# Wacky_Hat_Schematic.net
KiCad netlist of a schematic drawn in Altium Designer
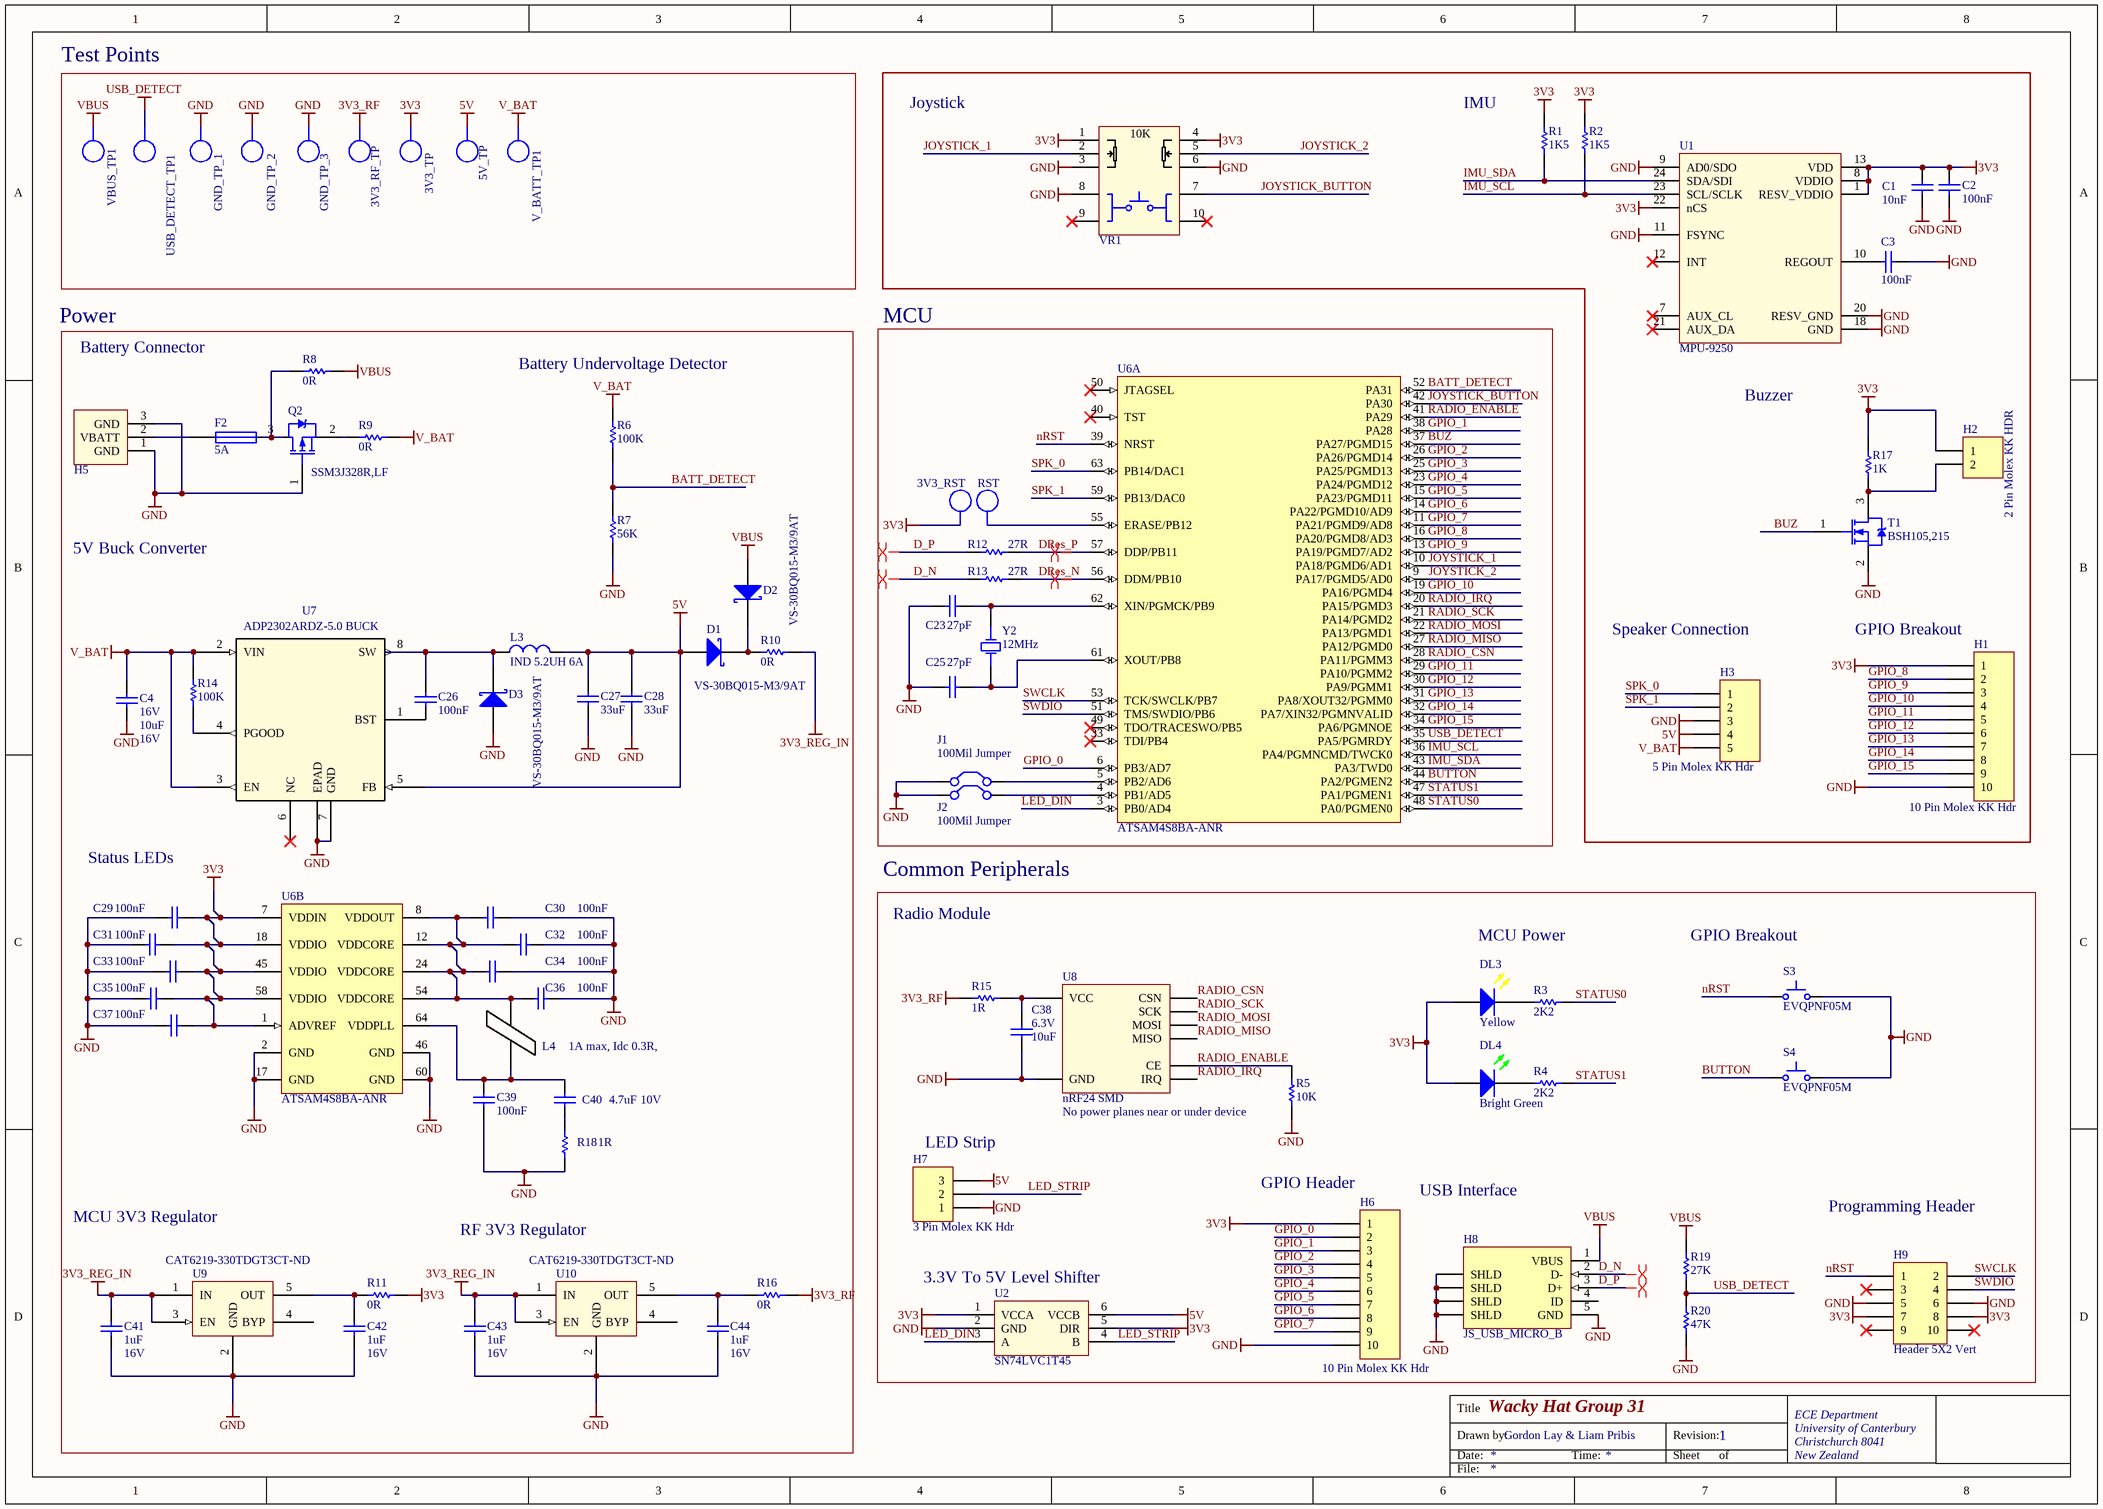
[diagram p0: Wacky Hat Schematic.SchDoc]

(export (version "E")
  (design (tool "Eeschema 10.0.6"))
  (components
    (comp (ref "3V3_RF_TP")
      (value "TP")
      (footprint "TP_1206")
      (description "Test-Point 3.3x1.6x2.1mm SMD")
      (fields
        (field (name "MANUFACTURER") "Harwin Inc")
        (field (name "MANUFACTURER PART NUMBER") "S1751-46R")
      )
      (libsource (lib "ECE AD19Components_19V1") (part "TP_1206"))
    )
    (comp (ref "3V3_RST")
      (value "TP")
      (footprint "TP_1206")
      (description "Test-Point 3.3x1.6x2.1mm SMD")
      (fields
        (field (name "MANUFACTURER") "Harwin Inc")
        (field (name "MANUFACTURER PART NUMBER") "S1751-46R")
      )
      (libsource (lib "ECE AD19Components_19V1") (part "TP_1206"))
    )
    (comp (ref "3V3_TP")
      (value "TP")
      (footprint "TP_1206")
      (description "Test-Point 3.3x1.6x2.1mm SMD")
      (fields
        (field (name "MANUFACTURER") "Harwin Inc")
        (field (name "MANUFACTURER PART NUMBER") "S1751-46R")
      )
      (libsource (lib "ECE AD19Components_19V1") (part "TP_1206"))
    )
    (comp (ref "5V_TP")
      (value "TP")
      (footprint "TP_1206")
      (description "Test-Point 3.3x1.6x2.1mm SMD")
      (fields
        (field (name "MANUFACTURER") "Harwin Inc")
        (field (name "MANUFACTURER PART NUMBER") "S1751-46R")
      )
      (libsource (lib "ECE AD19Components_19V1") (part "TP_1206"))
    )
    (comp (ref "C1")
      (value "10nF")
      (footprint "CAPC1608L")
      (description "CAP CER 10nF X7R +-10% 50V 0603")
      (libsource (lib "ECE AD19Components_19V1") (part "CC_10nF_0603"))
    )
    (comp (ref "C2")
      (value "100nF")
      (footprint "CAPC1608L")
      (description "CAP CER 100nF X7R +-10% 50V 0603")
      (libsource (lib "ECE AD19Components_19V1") (part "CC_100nF_0603"))
    )
    (comp (ref "C3")
      (value "100nF")
      (footprint "CAPC1608L")
      (description "CAP CER 100nF X7R +-10% 50V 0603")
      (libsource (lib "ECE AD19Components_19V1") (part "CC_100nF_0603"))
    )
    (comp (ref "C4")
      (value "10uF")
      (footprint "CAPC2012L")
      (description "CAP CER 10uF X5R 16V 0805")
      (fields
        (field (name "MANUFACTURER") "Samsung Electro-Mechanics")
        (field (name "MANUFACTURER PART NUMBER") "CL21A106KOQNNWE")
        (field (name "VOLTAGE - RATED") "16V")
        (field (name "MAX VOLTAGE") "16V")
      )
      (libsource (lib "ENCE461AD19_19V2") (part "CC_10uF_16V_0805"))
    )
    (comp (ref "C23")
      (value "27pF")
      (footprint "CAPC1608L")
      (description "CAP CER 27pF NPO/COG +-5% 50V 0603")
      (libsource (lib "ECE AD19Components_19V1") (part "CC_27pF_0603"))
    )
    (comp (ref "C25")
      (value "27pF")
      (footprint "CAPC1608L")
      (description "CAP CER 27pF NPO/COG +-5% 50V 0603")
      (libsource (lib "ECE AD19Components_19V1") (part "CC_27pF_0603"))
    )
    (comp (ref "C26")
      (value "100nF")
      (footprint "CAPC1608L")
      (description "CAP CER 100nF X7R +-10% 50V 0603")
      (libsource (lib "ECE AD19Components_19V1") (part "CC_100nF_0603"))
    )
    (comp (ref "C27")
      (value "33uF")
      (footprint "CAPC2012L")
      (description "CAP CER 33uF X5R 6V3 0805")
      (fields
        (field (name "MANUFACTURER") "TDK Corporation")
        (field (name "MANUFACTURER PART NUMBER") "C2012X5R0J336M125AC")
      )
      (libsource (lib "ENCE461AD19_19V2") (part "CC_33uF_6V3_0805"))
    )
    (comp (ref "C28")
      (value "33uF")
      (footprint "CAPC2012L")
      (description "CAP CER 33uF X5R 6V3 0805")
      (fields
        (field (name "MANUFACTURER") "TDK Corporation")
        (field (name "MANUFACTURER PART NUMBER") "C2012X5R0J336M125AC")
      )
      (libsource (lib "ENCE461AD19_19V2") (part "CC_33uF_6V3_0805"))
    )
    (comp (ref "C29")
      (value "100nF")
      (footprint "CAPC1608L")
      (description "CAP CER 100nF X7R +-10% 50V 0603")
      (libsource (lib "ECE AD19Components_19V1") (part "CC_100nF_0603"))
    )
    (comp (ref "C30")
      (value "100nF")
      (footprint "CAPC1608L")
      (description "CAP CER 100nF X7R +-10% 50V 0603")
      (libsource (lib "ECE AD19Components_19V1") (part "CC_100nF_0603"))
    )
    (comp (ref "C31")
      (value "100nF")
      (footprint "CAPC1608L")
      (description "CAP CER 100nF X7R +-10% 50V 0603")
      (libsource (lib "ECE AD19Components_19V1") (part "CC_100nF_0603"))
    )
    (comp (ref "C32")
      (value "100nF")
      (footprint "CAPC1608L")
      (description "CAP CER 100nF X7R +-10% 50V 0603")
      (libsource (lib "ECE AD19Components_19V1") (part "CC_100nF_0603"))
    )
    (comp (ref "C33")
      (value "100nF")
      (footprint "CAPC1608L")
      (description "CAP CER 100nF X7R +-10% 50V 0603")
      (libsource (lib "ECE AD19Components_19V1") (part "CC_100nF_0603"))
    )
    (comp (ref "C34")
      (value "100nF")
      (footprint "CAPC1608L")
      (description "CAP CER 100nF X7R +-10% 50V 0603")
      (libsource (lib "ECE AD19Components_19V1") (part "CC_100nF_0603"))
    )
    (comp (ref "C35")
      (value "100nF")
      (footprint "CAPC1608L")
      (description "CAP CER 100nF X7R +-10% 50V 0603")
      (libsource (lib "ECE AD19Components_19V1") (part "CC_100nF_0603"))
    )
    (comp (ref "C36")
      (value "100nF")
      (footprint "CAPC1608L")
      (description "CAP CER 100nF X7R +-10% 50V 0603")
      (libsource (lib "ECE AD19Components_19V1") (part "CC_100nF_0603"))
    )
    (comp (ref "C37")
      (value "100nF")
      (footprint "CAPC1608L")
      (description "CAP CER 100nF X7R +-10% 50V 0603")
      (libsource (lib "ECE AD19Components_19V1") (part "CC_100nF_0603"))
    )
    (comp (ref "C38")
      (value "10uF")
      (footprint "CAPC1608L")
      (description "CAP CER 10UF X5R +-20% 6V3 0603")
      (fields (field (name "VOLTAGE - RATED") "6.3V"))
      (libsource (lib "ECE AD19Components_19V1") (part "CC_10uF_0603"))
    )
    (comp (ref "C39")
      (value "100nF")
      (footprint "CAPC1608L")
      (description "CAP CER 100nF X7R +-10% 50V 0603")
      (libsource (lib "ECE AD19Components_19V1") (part "CC_100nF_0603"))
    )
    (comp (ref "C40")
      (value "4.7uF")
      (footprint "CAPC1608N")
      (description "CAP CER 4.7uF X5R +-20%  10V 0603")
      (fields (field (name "MAX VOLTAGE") "10V"))
      (libsource (lib "ECE AD19Components_19V1") (part "CC_4.7uF_0603"))
    )
    (comp (ref "C41")
      (value "1uF")
      (footprint "CAPC1608L")
      (description "CAP CER 1uF Y5V -20% +80% 16V 0603")
      (fields (field (name "MAX VOLTAGE") "16V"))
      (libsource (lib "ECE AD19Components_19V1") (part "CC_1uF_0603"))
    )
    (comp (ref "C42")
      (value "1uF")
      (footprint "CAPC1608L")
      (description "CAP CER 1uF Y5V -20% +80% 16V 0603")
      (fields (field (name "MAX VOLTAGE") "16V"))
      (libsource (lib "ECE AD19Components_19V1") (part "CC_1uF_0603"))
    )
    (comp (ref "C43")
      (value "1uF")
      (footprint "CAPC1608L")
      (description "CAP CER 1uF Y5V -20% +80% 16V 0603")
      (fields (field (name "MAX VOLTAGE") "16V"))
      (libsource (lib "ECE AD19Components_19V1") (part "CC_1uF_0603"))
    )
    (comp (ref "C44")
      (value "1uF")
      (footprint "CAPC1608L")
      (description "CAP CER 1uF Y5V -20% +80% 16V 0603")
      (fields (field (name "MAX VOLTAGE") "16V"))
      (libsource (lib "ECE AD19Components_19V1") (part "CC_1uF_0603"))
    )
    (comp (ref "D1")
      (value "VS-30BQ015-M3/9AT")
      (footprint "SMC")
      (description "DIODE, SCHOTTKY, 3A, 15V, DO-214AB / SMC")
      (fields (field (name "MANUFACTURER") "Vishay Semiconductors"))
      (libsource (lib "ECE AD19Components_19V1") (part "DS_VS-30BQ015-M3"))
    )
    (comp (ref "D2")
      (value "VS-30BQ015-M3/9AT")
      (footprint "SMC")
      (description "DIODE, SCHOTTKY, 3A, 15V, DO-214AB / SMC")
      (fields (field (name "MANUFACTURER") "Vishay Semiconductors"))
      (libsource (lib "ECE AD19Components_19V1") (part "DS_VS-30BQ015-M3"))
    )
    (comp (ref "D3")
      (value "VS-30BQ015-M3/9AT")
      (footprint "SMC")
      (description "DIODE, SCHOTTKY, 3A, 15V, DO-214AB / SMC")
      (fields (field (name "MANUFACTURER") "Vishay Semiconductors"))
      (libsource (lib "ECE AD19Components_19V1") (part "DS_VS-30BQ015-M3"))
    )
    (comp (ref "DL3")
      (value "Yellow")
      (footprint "WL-SMCW0603")
      (description "LED Yellow 120mcd 0603 SMD")
      (fields
        (field (name "MANUFACTURER") "WURTH ELEKTRONIK")
        (field (name "MANUFACTURER PART NUMBER") "150060YS75000")
        (field (name "LED COLOUR") "Yellow")
      )
      (libsource (lib "ECE AD19Components_19V1") (part "DL_150060YS75000"))
    )
    (comp (ref "DL4")
      (value "Bright Green")
      (footprint "WL-SMCW0603")
      (description "LED Bright Green 40mcd 0603 SMD")
      (fields
        (field (name "MANUFACTURER") "WURTH ELEKTRONIK")
        (field (name "MANUFACTURER PART NUMBER") "150060VS75000")
        (field (name "LED COLOUR") "Bright Green")
      )
      (libsource (lib "ECE AD19Components_19V1") (part "DL_150060VS75000"))
    )
    (comp (ref "F2")
      (value "5A")
      (footprint "RESC3216N")
      (description "Fuse 5.0A Fast Acting 1206 SMD")
      (fields (field (name "MANUFACTURER PART NUMBER") "C1F5") (field (name "MANUFACTURER") "Bel TRP"))
      (libsource (lib "ECE AD19Components_19V1") (part "FS_Fuse_5.0A"))
    )
    (comp (ref "GND_TP_1")
      (value "TP")
      (footprint "TP_1206")
      (description "Test-Point 3.3x1.6x2.1mm SMD")
      (fields
        (field (name "MANUFACTURER") "Harwin Inc")
        (field (name "MANUFACTURER PART NUMBER") "S1751-46R")
      )
      (libsource (lib "ECE AD19Components_19V1") (part "TP_1206"))
    )
    (comp (ref "GND_TP_2")
      (value "TP")
      (footprint "TP_1206")
      (description "Test-Point 3.3x1.6x2.1mm SMD")
      (fields
        (field (name "MANUFACTURER") "Harwin Inc")
        (field (name "MANUFACTURER PART NUMBER") "S1751-46R")
      )
      (libsource (lib "ECE AD19Components_19V1") (part "TP_1206"))
    )
    (comp (ref "GND_TP_3")
      (value "TP")
      (footprint "TP_1206")
      (description "Test-Point 3.3x1.6x2.1mm SMD")
      (fields
        (field (name "MANUFACTURER") "Harwin Inc")
        (field (name "MANUFACTURER PART NUMBER") "S1751-46R")
      )
      (libsource (lib "ECE AD19Components_19V1") (part "TP_1206"))
    )
    (comp (ref "H1")
      (value "10 Pin Molex KK Hdr")
      (footprint "MOLEX_KK_10_HDR")
      (description "CONN HEADER 10POS 2.54mm VERT_ Thru Hole")
      (libsource (lib "ECE AD19Components_19V1") (part "JA_MOLEX_KK_10POS"))
    )
    (comp (ref "H2")
      (value "2 Pin Molex KK HDR")
      (footprint "MOLEX_KK_2_HDR")
      (description "CONN HEADER 2POS 2.54mm VERT_Thru Hole")
      (libsource (lib "ECE AD19Components_19V1") (part "JA_MOLEX_KK_2POS"))
    )
    (comp (ref "H3")
      (value "5 Pin Molex KK Hdr")
      (footprint "MOLEX_KK_5_HDR")
      (description "CONN HEADER 5POS 2.54mm VERT_Thru Hole")
      (fields (field (name "MANUFACTURER") "Molex"))
      (libsource (lib "ECE AD19Components_19V1") (part "JA_MOLEX_KK_5POS"))
    )
    (comp (ref "H5")
      (value "Battery_HEADER_3pin")
      (footprint "BATT_HEADER_3POS")
      (description "3Pin Header 2.54mm spacing")
      (libsource (lib "ENCE461AD19_19V2") (part "Battery_HEADER_3pin"))
    )
    (comp (ref "H6")
      (value "10 Pin Molex KK Hdr")
      (footprint "MOLEX_KK_10_HDR")
      (description "CONN HEADER 10POS 2.54mm VERT_ Thru Hole")
      (libsource (lib "ECE AD19Components_19V1") (part "JA_MOLEX_KK_10POS"))
    )
    (comp (ref "H7")
      (value "3 Pin Molex KK Hdr")
      (footprint "MOLEX_KK_3_HDR")
      (description "CONN HEADER 3POS 2.54mm VERT_Thru Hole")
      (fields (field (name "MANUFACTURER") "Molex"))
      (libsource (lib "ECE AD19Components_19V1") (part "JA_MOLEX_KK_3POS"))
    )
    (comp (ref "H8")
      (value "JS_USB_MICRO_B")
      (footprint "FCI_USB_10118194-0001LF")
      (description "CONN USB MICRO B RECPT SMT R/A")
      (fields (field (name "MANUFACTURER") "FCI") (field (name "MANUFACTURER PART NUMBER") "10118194-0001LF"))
      (libsource (lib "ECE AD19Components_19V1") (part "JS_USB_MICRO_B_SMT"))
    )
    (comp (ref "H9")
      (value "Header 5X2 Vert")
      (footprint "IDC2.54-V10D")
      (description "IDC Header, 2,54mm, 10-Pin, Vert")
      (libsource (lib "ECE AD19Components_19V1") (part "JA_HDR_IDC_5X2_VERT"))
    )
    (comp (ref "J1")
      (value "100Mil Jumper")
      (footprint "JMP2.54")
      (description "2.54mm Jumper Thru Hole")
      (libsource (lib "ECE AD19Components_19V1") (part "TP_JUMPER"))
    )
    (comp (ref "J2")
      (value "100Mil Jumper")
      (footprint "JMP2.54")
      (description "2.54mm Jumper Thru Hole")
      (libsource (lib "ECE AD19Components_19V1") (part "TP_JUMPER"))
    )
    (comp (ref "L3")
      (value "IND 5.2UH 6A")
      (footprint "INDUCTOR5u2")
      (description "FIXED IND 5.2UH 6A 22 MOHM SMD")
      (fields
        (field (name "MANUFACTURER") "Sumida America Components Inc.")
        (field (name "MANUFACTURER PART NUMBER") "CDRH104RNP-5R2NC")
      )
      (libsource (lib "ENCE461AD19_19V2") (part "CDRH104RNP-5R2NC"))
    )
    (comp (ref "L4")
      (value "1A max, Idc 0.3R,")
      (footprint "INDC3216L")
      (description "Ferrite Bead, Rdc 0.3R, Z100MHZ 600R, Imax 1A, SMD 1206")
      (fields
        (field (name "MANUFACTURER") "FAIR-RITE")
        (field (name "MANUFACTURER PART NUMBER") "2512066017Y1")
      )
      (libsource (lib "ECE AD19Components_19V1") (part "IN_Ferrite-Bead"))
    )
    (comp (ref "Q2")
      (value "SSM3J328R,LF")
      (footprint "SOT23_L")
      (description "MOSFET P-CH 20V 6A SOT23-3")
      (fields
        (field (name "MANUFACTURER") "Toshiba")
        (field (name "MANUFACTURER PART NUMBER") "SSM3J328R,LF")
      )
      (libsource (lib "ECE AD19Components_19V1") (part "TM_SSM3J328R"))
    )
    (comp (ref "R1")
      (value "1K5")
      (footprint "RESC1608L")
      (description "RES 1.5K OHM 1/10W 5% 0603 SMD")
      (libsource (lib "ECE AD19Components_19V1") (part "RS_1K5"))
    )
    (comp (ref "R2")
      (value "1K5")
      (footprint "RESC1608L")
      (description "RES 1.5K OHM 1/10W 5% 0603 SMD")
      (libsource (lib "ECE AD19Components_19V1") (part "RS_1K5"))
    )
    (comp (ref "R3")
      (value "2K2")
      (footprint "RESC1608L")
      (description "RES 2.2K OHM 1/10W 5% 0603 SMD")
      (libsource (lib "ECE AD19Components_19V1") (part "RS_2K2"))
    )
    (comp (ref "R4")
      (value "2K2")
      (footprint "RESC1608L")
      (description "RES 2.2K OHM 1/10W 5% 0603 SMD")
      (libsource (lib "ECE AD19Components_19V1") (part "RS_2K2"))
    )
    (comp (ref "R5")
      (value "10K")
      (footprint "RESC1608L")
      (description "RES 10.0K OHM 1/10W 5% 0603 SMD")
      (libsource (lib "ECE AD19Components_19V1") (part "RS_10K"))
    )
    (comp (ref "R6")
      (value "100K")
      (footprint "RESC1608L")
      (description "RES 100K OHM 1/10W 5% 0603 SMD")
      (libsource (lib "ECE AD19Components_19V1") (part "RS_100K"))
    )
    (comp (ref "R7")
      (value "56K")
      (footprint "RESC1608L")
      (description "RES 56.0K OHM 1/10W 5% 0603 SMD")
      (libsource (lib "ECE AD19Components_19V1") (part "RS_56K"))
    )
    (comp (ref "R8")
      (value "0R")
      (footprint "RESC1608L")
      (description "RES 0.0 OHM 1/10W 5% 0603 SMD")
      (libsource (lib "ECE AD19Components_19V1") (part "RS_0R0"))
    )
    (comp (ref "R9")
      (value "0R")
      (footprint "RESC1608L")
      (description "RES 0.0 OHM 1/10W 5% 0603 SMD")
      (libsource (lib "ECE AD19Components_19V1") (part "RS_0R0"))
    )
    (comp (ref "R10")
      (value "0R")
      (footprint "RESC1608L")
      (description "RES 0.0 OHM 1/10W 5% 0603 SMD")
      (libsource (lib "ECE AD19Components_19V1") (part "RS_0R0"))
    )
    (comp (ref "R11")
      (value "0R")
      (footprint "RESC1608L")
      (description "RES 0.0 OHM 1/10W 5% 0603 SMD")
      (libsource (lib "ECE AD19Components_19V1") (part "RS_0R0"))
    )
    (comp (ref "R12")
      (value "27R")
      (footprint "RESC1608L")
      (description "RES 27 OHM 1/10W 5% 0603 SMD")
      (libsource (lib "ECE AD19Components_19V1") (part "RS_27R"))
    )
    (comp (ref "R13")
      (value "27R")
      (footprint "RESC1608L")
      (description "RES 27 OHM 1/10W 5% 0603 SMD")
      (libsource (lib "ECE AD19Components_19V1") (part "RS_27R"))
    )
    (comp (ref "R14")
      (value "100K")
      (footprint "RESC1608L")
      (description "RES 100K OHM 1/10W 5% 0603 SMD")
      (libsource (lib "ECE AD19Components_19V1") (part "RS_100K"))
    )
    (comp (ref "R15")
      (value "1R")
      (footprint "RESC3216L")
      (description "RES 1R OHM 1/4W 5% 1206 SMD")
      (libsource (lib "ECE AD19Components_19V1") (part "RT_1R"))
    )
    (comp (ref "R16")
      (value "0R")
      (footprint "RESC1608L")
      (description "RES 0.0 OHM 1/10W 5% 0603 SMD")
      (libsource (lib "ECE AD19Components_19V1") (part "RS_0R0"))
    )
    (comp (ref "R17")
      (value "1K")
      (footprint "RESC1608L")
      (description "RES 1.0K OHM 1/10W 5% 0603 SMD")
      (libsource (lib "ECE AD19Components_19V1") (part "RS_1K"))
    )
    (comp (ref "R18")
      (value "1R")
      (footprint "RESC3216L")
      (description "RES 1R OHM 1/4W 5% 1206 SMD")
      (libsource (lib "ECE AD19Components_19V1") (part "RT_1R"))
    )
    (comp (ref "R19")
      (value "27K")
      (footprint "RESC1608L")
      (description "RES 27K OHM 1/10W 5% 0603 SMD")
      (libsource (lib "ECE AD19Components_19V1") (part "RS_27K"))
    )
    (comp (ref "R20")
      (value "47K")
      (footprint "RESC1608L")
      (description "RES 47.0K OHM 1/10W 5% 0603 SMD")
      (libsource (lib "ECE AD19Components_19V1") (part "RS_47K"))
    )
    (comp (ref "RST")
      (value "TP")
      (footprint "TP_1206")
      (description "Test-Point 3.3x1.6x2.1mm SMD")
      (fields
        (field (name "MANUFACTURER") "Harwin Inc")
        (field (name "MANUFACTURER PART NUMBER") "S1751-46R")
      )
      (libsource (lib "ECE AD19Components_19V1") (part "TP_1206"))
    )
    (comp (ref "S3")
      (value "EVQPNF05M")
      (footprint "EVQPNF05M")
      (description "Panasonic 6 x 3.5mm SMD Light Touch Switch Type SMD")
      (fields (field (name "MANUFACTURER") "Panasonic"))
      (libsource (lib "ECE AD19Components_19V1") (part "WS_EVQPNF05M"))
    )
    (comp (ref "S4")
      (value "EVQPNF05M")
      (footprint "EVQPNF05M")
      (description "Panasonic 6 x 3.5mm SMD Light Touch Switch Type SMD")
      (fields (field (name "MANUFACTURER") "Panasonic"))
      (libsource (lib "ECE AD19Components_19V1") (part "WS_EVQPNF05M"))
    )
    (comp (ref "T1")
      (value "BSH105,215")
      (footprint "SOT23_L")
      (description "MOSFET N-CH 20V 1.05A SOT-23")
      (fields
        (field (name "MANUFACTURER") "NXP Semiconductors")
        (field (name "MANUFACTURER PART NUMBER") "BSH105,215")
      )
      (libsource (lib "ECE AD19Components_19V1") (part "TM_BSH105"))
    )
    (comp (ref "U1")
      (value "MPU-9250")
      (footprint "Quad24")
      (description "9 axis IMU")
      (libsource (lib "ENCE461AD19_19V2") (part "MPU-9250"))
    )
    (comp (ref "U2")
      (value "SN74LVC1T45")
      (footprint "SOT23-6_N")
      (description "1.8V - 5V level converter")
      (libsource (lib "ENCE461_extras_2020") (part "SN74LVC1T45"))
    )
    (comp (ref "U6")
      (value "ATSAM4S8BA-ANR")
      (footprint "LQFP64_L")
      (description "IC MCU 32BIT 512KB FLASH 64LQFP")
      (fields (field (name "MANUFACTURER") "Atmel"))
      (libsource (lib "ECE AD19Components_19V1") (part "SE_ATSAM4S16BA-MU"))
    )
    (comp (ref "U7")
      (value "ADP2302ARDZ-5.0 BUCK")
      (footprint "RD_8_1")
      (description "IC REG BUCK 5V 2A 8SOIC")
      (fields (field (name "MANUFACTURER_PART_NUMBER") "ADP2302ARDZ-5.0-R7"))
      (libsource (lib "ENCE461AD19_19V2") (part "ADP2302ARDZ-5.0-R7"))
    )
    (comp (ref "U8")
      (value "nRF24 SMD")
      (footprint "NRF24")
      (description "nRF24 SMD Module")
      (fields (field (name "WARNING") "No power planes near or under device"))
      (libsource (lib "ENCE461AD19_19V2") (part "NRF24"))
    )
    (comp (ref "U9")
      (value "CAT6219-330TDGT3")
      (footprint "SOT95P280X145-5N")
      (description "IC REG LIN 3.3V 500MA TSOT23-5")
      (fields
        (field (name "BASE PART NUMBER") "CAT6219")
        (field (name "SUPPLIER PART NUMBER") "CAT6219-330TDGT3CT-ND")
      )
      (libsource (lib "ENCE461AD19_19V2") (part "SV_CAT6219-330TDGT3"))
    )
    (comp (ref "U10")
      (value "CAT6219-330TDGT3")
      (footprint "SOT95P280X145-5N")
      (description "IC REG LIN 3.3V 500MA TSOT23-5")
      (fields
        (field (name "BASE PART NUMBER") "CAT6219")
        (field (name "SUPPLIER PART NUMBER") "CAT6219-330TDGT3CT-ND")
      )
      (libsource (lib "ENCE461AD19_19V2") (part "SV_CAT6219-330TDGT3"))
    )
    (comp (ref "USB_DETECT_TP1")
      (value "TP")
      (footprint "TP_1206")
      (description "Test-Point 3.3x1.6x2.1mm SMD")
      (fields
        (field (name "MANUFACTURER") "Harwin Inc")
        (field (name "MANUFACTURER PART NUMBER") "S1751-46R")
      )
      (libsource (lib "ECE AD19Components_19V1") (part "TP_1206"))
    )
    (comp (ref "VBUS_TP1")
      (value "TP")
      (footprint "TP_1206")
      (description "Test-Point 3.3x1.6x2.1mm SMD")
      (fields
        (field (name "MANUFACTURER") "Harwin Inc")
        (field (name "MANUFACTURER PART NUMBER") "S1751-46R")
      )
      (libsource (lib "ECE AD19Components_19V1") (part "TP_1206"))
    )
    (comp (ref "VR1")
      (value "Joystick 10k with Sw")
      (footprint "Joystick_Sw")
      (description "JOYSTICK 10K OHM 2 AXIS TH")
      (libsource (lib "ENCE461AD19_19V2") (part "Joystick 10k with Sw"))
    )
    (comp (ref "V_BATT_TP1")
      (value "TP")
      (footprint "TP_1206")
      (description "Test-Point 3.3x1.6x2.1mm SMD")
      (fields
        (field (name "MANUFACTURER") "Harwin Inc")
        (field (name "MANUFACTURER PART NUMBER") "S1751-46R")
      )
      (libsource (lib "ECE AD19Components_19V1") (part "TP_1206"))
    )
    (comp (ref "Y2")
      (value "12MHz")
      (footprint "6.0X3.5-4")
      (description "CRYSTAL 12MHZ 18PF 6X3.5mm SMD")
      (fields
        (field (name "MANUFACTURER") "CTS-Frequency Controls")
        (field (name "MANUFACTURER PART NUMBER") "406C35D12M00000")
        (field (name "FREQUENCY") "12MHz")
      )
      (libsource (lib "ECE AD19Components_19V1") (part "XT_CRYSTAL_12MHz_18pF"))
    )
  )
  (nets
    (net (code "1") (name "/BATT_DETECT") (class "Default")
      (node (ref "R6") (pin "1") (pinfunction "1_1") (pintype "passive"))
      (node (ref "R7") (pin "2") (pinfunction "2_2") (pintype "passive"))
      (node (ref "U6") (pin "52") (pinfunction "PA31_52") (pintype "bidirectional"))
    )
    (net (code "2") (name "/BUTTON") (class "Default")
      (node (ref "S4") (pin "1") (pintype "passive"))
      (node (ref "U6") (pin "44") (pinfunction "PA2/PGMEN2_44") (pintype "bidirectional"))
    )
    (net (code "3") (name "/BUZ") (class "Default")
      (node (ref "T1") (pin "1") (pinfunction "1_1") (pintype "passive"))
      (node (ref "U6") (pin "37") (pinfunction "PA27/PGMD15_37") (pintype "bidirectional"))
    )
    (net (code "4") (name "/DRes_N") (class "Default")
      (node (ref "R13") (pin "2") (pinfunction "2_2") (pintype "passive"))
      (node (ref "U6") (pin "56") (pinfunction "DDM/PB10_56") (pintype "bidirectional"))
    )
    (net (code "5") (name "/DRes_P") (class "Default")
      (node (ref "R12") (pin "2") (pinfunction "2_2") (pintype "passive"))
      (node (ref "U6") (pin "57") (pinfunction "DDP/PB11_57") (pintype "bidirectional"))
    )
    (net (code "6") (name "/D_N") (class "Default")
      (node (ref "H8") (pin "2") (pinfunction "D-_2") (pintype "input"))
      (node (ref "R13") (pin "1") (pinfunction "1_1") (pintype "passive"))
    )
    (net (code "7") (name "/D_P") (class "Default")
      (node (ref "H8") (pin "3") (pinfunction "D+_3") (pintype "input"))
      (node (ref "R12") (pin "1") (pinfunction "1_1") (pintype "passive"))
    )
    (net (code "8") (name "/GPIO_0") (class "Default")
      (node (ref "H6") (pin "2") (pinfunction "2_2") (pintype "passive"))
      (node (ref "U6") (pin "6") (pinfunction "PB3/AD7_6") (pintype "bidirectional"))
    )
    (net (code "9") (name "/GPIO_1") (class "Default")
      (node (ref "H6") (pin "3") (pinfunction "3_3") (pintype "passive"))
      (node (ref "U6") (pin "38") (pinfunction "PA28_38") (pintype "bidirectional"))
    )
    (net (code "10") (name "/GPIO_2") (class "Default")
      (node (ref "H6") (pin "4") (pinfunction "4_4") (pintype "passive"))
      (node (ref "U6") (pin "26") (pinfunction "PA26/PGMD14_26") (pintype "bidirectional"))
    )
    (net (code "11") (name "/GPIO_3") (class "Default")
      (node (ref "H6") (pin "5") (pinfunction "5_5") (pintype "passive"))
      (node (ref "U6") (pin "25") (pinfunction "PA25/PGMD13_25") (pintype "bidirectional"))
    )
    (net (code "12") (name "/GPIO_4") (class "Default")
      (node (ref "H6") (pin "6") (pinfunction "6_6") (pintype "passive"))
      (node (ref "U6") (pin "23") (pinfunction "PA24/PGMD12_23") (pintype "bidirectional"))
    )
    (net (code "13") (name "/GPIO_5") (class "Default")
      (node (ref "H6") (pin "7") (pinfunction "7_7") (pintype "passive"))
      (node (ref "U6") (pin "15") (pinfunction "PA23/PGMD11_15") (pintype "bidirectional"))
    )
    (net (code "14") (name "/GPIO_6") (class "Default")
      (node (ref "H6") (pin "8") (pinfunction "8_8") (pintype "passive"))
      (node (ref "U6") (pin "14") (pinfunction "PA22/PGMD10/AD9_14") (pintype "bidirectional"))
    )
    (net (code "15") (name "/GPIO_7") (class "Default")
      (node (ref "H6") (pin "9") (pinfunction "9_9") (pintype "passive"))
      (node (ref "U6") (pin "11") (pinfunction "PA21/PGMD9/AD8_11") (pintype "bidirectional"))
    )
    (net (code "16") (name "/GPIO_8") (class "Default")
      (node (ref "H1") (pin "2") (pinfunction "2_2") (pintype "passive"))
      (node (ref "U6") (pin "16") (pinfunction "PA20/PGMD8/AD3_16") (pintype "bidirectional"))
    )
    (net (code "17") (name "/GPIO_9") (class "Default")
      (node (ref "H1") (pin "3") (pinfunction "3_3") (pintype "passive"))
      (node (ref "U6") (pin "13") (pinfunction "PA19/PGMD7/AD2_13") (pintype "bidirectional"))
    )
    (net (code "18") (name "/GPIO_10") (class "Default")
      (node (ref "H1") (pin "4") (pinfunction "4_4") (pintype "passive"))
      (node (ref "U6") (pin "19") (pinfunction "PA16/PGMD4_19") (pintype "bidirectional"))
    )
    (net (code "19") (name "/GPIO_11") (class "Default")
      (node (ref "H1") (pin "5") (pinfunction "5_5") (pintype "passive"))
      (node (ref "U6") (pin "29") (pinfunction "PA10/PGMM2_29") (pintype "bidirectional"))
    )
    (net (code "20") (name "/GPIO_12") (class "Default")
      (node (ref "H1") (pin "6") (pinfunction "6_6") (pintype "passive"))
      (node (ref "U6") (pin "30") (pinfunction "PA9/PGMM1_30") (pintype "bidirectional"))
    )
    (net (code "21") (name "/GPIO_13") (class "Default")
      (node (ref "H1") (pin "7") (pinfunction "7_7") (pintype "passive"))
      (node (ref "U6") (pin "31") (pinfunction "PA8/XOUT32/PGMM0_31") (pintype "bidirectional"))
    )
    (net (code "22") (name "/GPIO_14") (class "Default")
      (node (ref "H1") (pin "8") (pinfunction "8_8") (pintype "passive"))
      (node (ref "U6") (pin "32") (pinfunction "PA7/XIN32/PGMNVALID_32") (pintype "bidirectional"))
    )
    (net (code "23") (name "/GPIO_15") (class "Default")
      (node (ref "H1") (pin "9") (pinfunction "9_9") (pintype "passive"))
      (node (ref "U6") (pin "34") (pinfunction "PA6/PGMNOE_34") (pintype "bidirectional"))
    )
    (net (code "24") (name "/IMU_SCL") (class "Default")
      (node (ref "R2") (pin "1") (pinfunction "1_1") (pintype "passive"))
      (node (ref "U1") (pin "23") (pinfunction "SCL/SCLK_23") (pintype "passive"))
      (node (ref "U6") (pin "36") (pinfunction "PA4/PGMNCMD/TWCK0_36") (pintype "bidirectional"))
    )
    (net (code "25") (name "/IMU_SDA") (class "Default")
      (node (ref "R1") (pin "1") (pinfunction "1_1") (pintype "passive"))
      (node (ref "U1") (pin "24") (pinfunction "SDA/SDI_24") (pintype "passive"))
      (node (ref "U6") (pin "43") (pinfunction "PA3/TWD0_43") (pintype "bidirectional"))
    )
    (net (code "26") (name "/JOYSTICK_1") (class "Default")
      (node (ref "U6") (pin "10") (pinfunction "PA18/PGMD6/AD1_10") (pintype "bidirectional"))
      (node (ref "VR1") (pin "2") (pinfunction "2_2") (pintype "passive"))
    )
    (net (code "27") (name "/JOYSTICK_2") (class "Default")
      (node (ref "U6") (pin "9") (pinfunction "PA17/PGMD5/AD0_9") (pintype "bidirectional"))
      (node (ref "VR1") (pin "5") (pinfunction "2'_5") (pintype "passive"))
    )
    (net (code "28") (name "/JOYSTICK_BUTTON") (class "Default")
      (node (ref "U6") (pin "42") (pinfunction "PA30_42") (pintype "bidirectional"))
      (node (ref "VR1") (pin "7") (pinfunction "7_7") (pintype "passive"))
    )
    (net (code "29") (name "/LED_DIN") (class "Default")
      (node (ref "U2") (pin "3") (pinfunction "A_3") (pintype "passive"))
      (node (ref "U6") (pin "3") (pinfunction "PB0/AD4_3") (pintype "bidirectional"))
    )
    (net (code "30") (name "/LED_STRIP") (class "Default")
      (node (ref "H7") (pin "2") (pinfunction "2_2") (pintype "passive"))
      (node (ref "U2") (pin "4") (pinfunction "B_4") (pintype "passive"))
    )
    (net (code "31") (name "/RADIO_CSN") (class "Default")
      (node (ref "U6") (pin "28") (pinfunction "PA11/PGMM3_28") (pintype "bidirectional"))
      (node (ref "U8") (pin "4") (pinfunction "CSN_4") (pintype "passive"))
    )
    (net (code "32") (name "/RADIO_ENABLE") (class "Default")
      (node (ref "R5") (pin "2") (pinfunction "2_2") (pintype "passive"))
      (node (ref "U6") (pin "41") (pinfunction "PA29_41") (pintype "bidirectional"))
      (node (ref "U8") (pin "3") (pinfunction "CE_3") (pintype "passive"))
    )
    (net (code "33") (name "/RADIO_IRQ") (class "Default")
      (node (ref "U6") (pin "20") (pinfunction "PA15/PGMD3_20") (pintype "bidirectional"))
      (node (ref "U8") (pin "8") (pinfunction "IRQ_8") (pintype "passive"))
    )
    (net (code "34") (name "/RADIO_MISO") (class "Default")
      (node (ref "U6") (pin "27") (pinfunction "PA12/PGMD0_27") (pintype "bidirectional"))
      (node (ref "U8") (pin "7") (pinfunction "MISO_7") (pintype "passive"))
    )
    (net (code "35") (name "/RADIO_MOSI") (class "Default")
      (node (ref "U6") (pin "22") (pinfunction "PA13/PGMD1_22") (pintype "bidirectional"))
      (node (ref "U8") (pin "6") (pinfunction "MOSI_6") (pintype "passive"))
    )
    (net (code "36") (name "/RADIO_SCK") (class "Default")
      (node (ref "U6") (pin "21") (pinfunction "PA14/PGMD2_21") (pintype "bidirectional"))
      (node (ref "U8") (pin "5") (pinfunction "SCK_5") (pintype "passive"))
    )
    (net (code "37") (name "/SPK_0") (class "Default")
      (node (ref "H3") (pin "1") (pinfunction "1_1") (pintype "passive"))
      (node (ref "U6") (pin "63") (pinfunction "PB14/DAC1_63") (pintype "bidirectional"))
    )
    (net (code "38") (name "/SPK_1") (class "Default")
      (node (ref "H3") (pin "2") (pinfunction "2_2") (pintype "passive"))
      (node (ref "U6") (pin "59") (pinfunction "PB13/DAC0_59") (pintype "bidirectional"))
    )
    (net (code "39") (name "/STATUS0") (class "Default")
      (node (ref "R3") (pin "2") (pinfunction "2_2") (pintype "passive"))
      (node (ref "U6") (pin "48") (pinfunction "PA0/PGMEN0_48") (pintype "bidirectional"))
    )
    (net (code "40") (name "/STATUS1") (class "Default")
      (node (ref "R4") (pin "2") (pinfunction "2_2") (pintype "passive"))
      (node (ref "U6") (pin "47") (pinfunction "PA1/PGMEN1_47") (pintype "bidirectional"))
    )
    (net (code "41") (name "/SWCLK") (class "Default")
      (node (ref "H9") (pin "2") (pinfunction "2_2") (pintype "passive"))
      (node (ref "U6") (pin "53") (pinfunction "TCK/SWCLK/PB7_53") (pintype "bidirectional"))
    )
    (net (code "42") (name "/SWDIO") (class "Default")
      (node (ref "H9") (pin "4") (pinfunction "4_4") (pintype "passive"))
      (node (ref "U6") (pin "51") (pinfunction "TMS/SWDIO/PB6_51") (pintype "bidirectional"))
    )
    (net (code "43") (name "/nRST") (class "Default")
      (node (ref "H9") (pin "1") (pinfunction "1_1") (pintype "passive"))
      (node (ref "S3") (pin "1") (pintype "passive"))
      (node (ref "U6") (pin "39") (pinfunction "NRST_39") (pintype "bidirectional"))
    )
    (net (code "44") (name "3V3") (class "Default")
      (node (ref "3V3_RST") (pin "1") (pinfunction "1_1") (pintype "passive"))
      (node (ref "3V3_TP") (pin "1") (pinfunction "1_1") (pintype "passive"))
      (node (ref "C1") (pin "2") (pinfunction "2_2") (pintype "passive"))
      (node (ref "C2") (pin "2") (pinfunction "2_2") (pintype "passive"))
      (node (ref "C29") (pin "2") (pinfunction "2_2") (pintype "passive"))
      (node (ref "C31") (pin "2") (pinfunction "2_2") (pintype "passive"))
      (node (ref "C33") (pin "2") (pinfunction "2_2") (pintype "passive"))
      (node (ref "C35") (pin "2") (pinfunction "2_2") (pintype "passive"))
      (node (ref "C37") (pin "2") (pinfunction "2_2") (pintype "passive"))
      (node (ref "DL3") (pin "2") (pinfunction "A_2") (pintype "passive"))
      (node (ref "DL4") (pin "2") (pinfunction "A_2") (pintype "passive"))
      (node (ref "H1") (pin "1") (pinfunction "1_1") (pintype "passive"))
      (node (ref "H2") (pin "1") (pinfunction "1_1") (pintype "passive"))
      (node (ref "H6") (pin "1") (pinfunction "1_1") (pintype "passive"))
      (node (ref "H9") (pin "7") (pinfunction "7_7") (pintype "passive"))
      (node (ref "H9") (pin "8") (pinfunction "8_8") (pintype "passive"))
      (node (ref "R1") (pin "2") (pinfunction "2_2") (pintype "passive"))
      (node (ref "R11") (pin "2") (pinfunction "2_2") (pintype "passive"))
      (node (ref "R17") (pin "2") (pinfunction "2_2") (pintype "passive"))
      (node (ref "R2") (pin "2") (pinfunction "2_2") (pintype "passive"))
      (node (ref "U1") (pin "1") (pinfunction "RESV_VDDIO_1") (pintype "passive"))
      (node (ref "U1") (pin "13") (pinfunction "VDD_13") (pintype "passive"))
      (node (ref "U1") (pin "22") (pinfunction "nCS_22") (pintype "passive"))
      (node (ref "U1") (pin "8") (pinfunction "VDDIO_8") (pintype "passive"))
      (node (ref "U2") (pin "1") (pinfunction "VCCA_1") (pintype "passive"))
      (node (ref "U2") (pin "5") (pinfunction "DIR_5") (pintype "passive"))
      (node (ref "U6") (pin "1") (pinfunction "ADVREF_1") (pintype "input"))
      (node (ref "U6") (pin "18") (pinfunction "VDDIO_18") (pintype "power_in"))
      (node (ref "U6") (pin "45") (pinfunction "VDDIO_45") (pintype "power_in"))
      (node (ref "U6") (pin "58") (pinfunction "VDDIO_58") (pintype "power_in"))
      (node (ref "U6") (pin "7") (pinfunction "VDDIN_7") (pintype "power_in"))
      (node (ref "VR1") (pin "1") (pinfunction "1_1") (pintype "passive"))
      (node (ref "VR1") (pin "4") (pinfunction "1'_4") (pintype "passive"))
    )
    (net (code "45") (name "3V3_REG_IN") (class "Default")
      (node (ref "C41") (pin "2") (pinfunction "2_2") (pintype "passive"))
      (node (ref "C43") (pin "2") (pinfunction "2_2") (pintype "passive"))
      (node (ref "R10") (pin "2") (pinfunction "2_2") (pintype "passive"))
      (node (ref "U10") (pin "1") (pinfunction "IN_1") (pintype "power_in"))
      (node (ref "U10") (pin "3") (pinfunction "EN_3") (pintype "input"))
      (node (ref "U9") (pin "1") (pinfunction "IN_1") (pintype "power_in"))
      (node (ref "U9") (pin "3") (pinfunction "EN_3") (pintype "input"))
    )
    (net (code "46") (name "3V3_RF") (class "Default")
      (node (ref "3V3_RF_TP") (pin "1") (pinfunction "1_1") (pintype "passive"))
      (node (ref "R15") (pin "1") (pinfunction "1_1") (pintype "passive"))
      (node (ref "R16") (pin "2") (pinfunction "2_2") (pintype "passive"))
    )
    (net (code "47") (name "5V") (class "Default")
      (node (ref "5V_TP") (pin "1") (pinfunction "1_1") (pintype "passive"))
      (node (ref "C27") (pin "2") (pinfunction "2_2") (pintype "passive"))
      (node (ref "C28") (pin "2") (pinfunction "2_2") (pintype "passive"))
      (node (ref "D1") (pin "1") (pinfunction "A_1") (pintype "passive"))
      (node (ref "H3") (pin "4") (pinfunction "4_4") (pintype "passive"))
      (node (ref "H7") (pin "3") (pinfunction "3_3") (pintype "passive"))
      (node (ref "L3") (pin "2") (pintype "passive"))
      (node (ref "U2") (pin "6") (pinfunction "VCCB_6") (pintype "passive"))
      (node (ref "U7") (pin "5") (pinfunction "FB_5") (pintype "input"))
    )
    (net (code "48") (name "GND") (class "Default")
      (node (ref "C1") (pin "1") (pinfunction "1_1") (pintype "passive"))
      (node (ref "C2") (pin "1") (pinfunction "1_1") (pintype "passive"))
      (node (ref "C23") (pin "1") (pinfunction "1_1") (pintype "passive"))
      (node (ref "C25") (pin "1") (pinfunction "1_1") (pintype "passive"))
      (node (ref "C27") (pin "1") (pinfunction "1_1") (pintype "passive"))
      (node (ref "C28") (pin "1") (pinfunction "1_1") (pintype "passive"))
      (node (ref "C29") (pin "1") (pinfunction "1_1") (pintype "passive"))
      (node (ref "C3") (pin "2") (pinfunction "2_2") (pintype "passive"))
      (node (ref "C30") (pin "2") (pinfunction "2_2") (pintype "passive"))
      (node (ref "C31") (pin "1") (pinfunction "1_1") (pintype "passive"))
      (node (ref "C32") (pin "2") (pinfunction "2_2") (pintype "passive"))
      (node (ref "C33") (pin "1") (pinfunction "1_1") (pintype "passive"))
      (node (ref "C34") (pin "2") (pinfunction "2_2") (pintype "passive"))
      (node (ref "C35") (pin "1") (pinfunction "1_1") (pintype "passive"))
      (node (ref "C36") (pin "2") (pinfunction "2_2") (pintype "passive"))
      (node (ref "C37") (pin "1") (pinfunction "1_1") (pintype "passive"))
      (node (ref "C38") (pin "1") (pinfunction "1_1") (pintype "passive"))
      (node (ref "C39") (pin "1") (pinfunction "1_1") (pintype "passive"))
      (node (ref "C4") (pin "1") (pinfunction "1_1") (pintype "passive"))
      (node (ref "C41") (pin "1") (pinfunction "1_1") (pintype "passive"))
      (node (ref "C42") (pin "1") (pinfunction "1_1") (pintype "passive"))
      (node (ref "C43") (pin "1") (pinfunction "1_1") (pintype "passive"))
      (node (ref "C44") (pin "1") (pinfunction "1_1") (pintype "passive"))
      (node (ref "D3") (pin "1") (pinfunction "A_1") (pintype "passive"))
      (node (ref "GND_TP_1") (pin "1") (pinfunction "1_1") (pintype "passive"))
      (node (ref "GND_TP_2") (pin "1") (pinfunction "1_1") (pintype "passive"))
      (node (ref "GND_TP_3") (pin "1") (pinfunction "1_1") (pintype "passive"))
      (node (ref "H1") (pin "10") (pinfunction "10_10") (pintype "passive"))
      (node (ref "H3") (pin "3") (pinfunction "3_3") (pintype "passive"))
      (node (ref "H5") (pin "1") (pinfunction "GND_1") (pintype "passive"))
      (node (ref "H5") (pin "3") (pinfunction "GND_3") (pintype "passive"))
      (node (ref "H6") (pin "10") (pinfunction "10_10") (pintype "passive"))
      (node (ref "H7") (pin "1") (pinfunction "1_1") (pintype "passive"))
      (node (ref "H8") (pin "5") (pinfunction "GND_5") (pintype "passive"))
      (node (ref "H8") (pin "6") (pinfunction "SHLD_6") (pintype "passive"))
      (node (ref "H9") (pin "5") (pinfunction "5_5") (pintype "passive"))
      (node (ref "H9") (pin "6") (pinfunction "6_6") (pintype "passive"))
      (node (ref "J1") (pin "1") (pinfunction "C1_1") (pintype "passive"))
      (node (ref "J2") (pin "1") (pinfunction "C1_1") (pintype "passive"))
      (node (ref "Q2") (pin "1") (pinfunction "1_1") (pintype "passive"))
      (node (ref "R18") (pin "1") (pinfunction "1_1") (pintype "passive"))
      (node (ref "R20") (pin "1") (pinfunction "1_1") (pintype "passive"))
      (node (ref "R5") (pin "1") (pinfunction "1_1") (pintype "passive"))
      (node (ref "R7") (pin "1") (pinfunction "1_1") (pintype "passive"))
      (node (ref "S3") (pin "2") (pintype "passive"))
      (node (ref "S4") (pin "2") (pintype "passive"))
      (node (ref "T1") (pin "2") (pinfunction "2_2") (pintype "passive"))
      (node (ref "U1") (pin "11") (pinfunction "FSYNC_11") (pintype "passive"))
      (node (ref "U1") (pin "18") (pinfunction "GND_18") (pintype "passive"))
      (node (ref "U1") (pin "20") (pinfunction "RESV_GND_20") (pintype "passive"))
      (node (ref "U1") (pin "9") (pinfunction "AD0/SDO_9") (pintype "passive"))
      (node (ref "U10") (pin "2") (pinfunction "GND_2") (pintype "power_in"))
      (node (ref "U2") (pin "2") (pinfunction "GND_2") (pintype "passive"))
      (node (ref "U6") (pin "17") (pinfunction "GND_17") (pintype "power_in"))
      (node (ref "U6") (pin "2") (pinfunction "GND_2") (pintype "power_in"))
      (node (ref "U6") (pin "46") (pinfunction "GND_46") (pintype "power_in"))
      (node (ref "U6") (pin "60") (pinfunction "GND_60") (pintype "power_in"))
      (node (ref "U7") (pin "7") (pinfunction "GND_7") (pintype "power_in"))
      (node (ref "U7") (pin "EPAD") (pinfunction "EPAD_EPAD") (pintype "passive"))
      (node (ref "U8") (pin "2") (pinfunction "GND_2") (pintype "passive"))
      (node (ref "U9") (pin "2") (pinfunction "GND_2") (pintype "power_in"))
      (node (ref "VR1") (pin "3") (pinfunction "3_3") (pintype "passive"))
      (node (ref "VR1") (pin "6") (pinfunction "3'_6") (pintype "passive"))
      (node (ref "VR1") (pin "8") (pinfunction "8_8") (pintype "passive"))
    )
    (net (code "49") (name "Net-(C40-Pad1)") (class "Default")
      (node (ref "C40") (pin "1") (pinfunction "1_1") (pintype "passive"))
      (node (ref "R18") (pin "2") (pinfunction "2_2") (pintype "passive"))
    )
    (net (code "50") (name "Net-(D1-K)") (class "Default")
      (node (ref "D1") (pin "2") (pinfunction "K_2") (pintype "passive"))
      (node (ref "D2") (pin "2") (pinfunction "K_2") (pintype "passive"))
      (node (ref "R10") (pin "1") (pinfunction "1_1") (pintype "passive"))
    )
    (net (code "51") (name "Net-(D3-K)") (class "Default")
      (node (ref "C26") (pin "2") (pinfunction "2_2") (pintype "passive"))
      (node (ref "D3") (pin "2") (pinfunction "K_2") (pintype "passive"))
      (node (ref "L3") (pin "1") (pintype "passive"))
      (node (ref "U7") (pin "8") (pinfunction "SW_8") (pintype "output"))
    )
    (net (code "52") (name "Net-(DL3-K)") (class "Default")
      (node (ref "DL3") (pin "1") (pinfunction "K_1") (pintype "passive"))
      (node (ref "R3") (pin "1") (pinfunction "1_1") (pintype "passive"))
    )
    (net (code "53") (name "Net-(DL4-K)") (class "Default")
      (node (ref "DL4") (pin "1") (pinfunction "K_1") (pintype "passive"))
      (node (ref "R4") (pin "1") (pinfunction "1_1") (pintype "passive"))
    )
    (net (code "54") (name "Net-(F2-Pad2)") (class "Default")
      (node (ref "F2") (pin "2") (pinfunction "2_2") (pintype "passive"))
      (node (ref "Q2") (pin "3") (pinfunction "3_3") (pintype "passive"))
      (node (ref "R8") (pin "1") (pinfunction "1_1") (pintype "passive"))
    )
    (net (code "55") (name "Net-(H2-Pad2)") (class "Default")
      (node (ref "H2") (pin "2") (pinfunction "2_2") (pintype "passive"))
      (node (ref "R17") (pin "1") (pinfunction "1_1") (pintype "passive"))
      (node (ref "T1") (pin "3") (pinfunction "3_3") (pintype "passive"))
    )
    (net (code "56") (name "Net-(H5-VBATT)") (class "Default")
      (node (ref "F2") (pin "1") (pinfunction "1_1") (pintype "passive"))
      (node (ref "H5") (pin "2") (pinfunction "VBATT_2") (pintype "passive"))
    )
    (net (code "57") (name "Net-(J1-C2)") (class "Default")
      (node (ref "J1") (pin "2") (pinfunction "C2_2") (pintype "passive"))
      (node (ref "U6") (pin "5") (pinfunction "PB2/AD6_5") (pintype "bidirectional"))
    )
    (net (code "58") (name "Net-(J2-C2)") (class "Default")
      (node (ref "J2") (pin "2") (pinfunction "C2_2") (pintype "passive"))
      (node (ref "U6") (pin "4") (pinfunction "PB1/AD5_4") (pintype "bidirectional"))
    )
    (net (code "59") (name "Net-(Q2-Pad2)") (class "Default")
      (node (ref "Q2") (pin "2") (pinfunction "2_2") (pintype "passive"))
      (node (ref "R9") (pin "1") (pinfunction "1_1") (pintype "passive"))
    )
    (net (code "60") (name "Net-(U1-REGOUT)") (class "Default")
      (node (ref "C3") (pin "1") (pinfunction "1_1") (pintype "passive"))
      (node (ref "U1") (pin "10") (pinfunction "REGOUT_10") (pintype "passive"))
    )
    (net (code "61") (name "Net-(U6A-ERASE{slash}PB12)") (class "Default")
      (node (ref "RST") (pin "1") (pinfunction "1_1") (pintype "passive"))
      (node (ref "U6") (pin "55") (pinfunction "ERASE/PB12_55") (pintype "bidirectional"))
    )
    (net (code "62") (name "Net-(U6A-XIN{slash}PGMCK{slash}PB9)") (class "Default")
      (node (ref "C23") (pin "2") (pinfunction "2_2") (pintype "passive"))
      (node (ref "U6") (pin "62") (pinfunction "XIN/PGMCK/PB9_62") (pintype "bidirectional"))
      (node (ref "Y2") (pin "1") (pinfunction "OSC1_1") (pintype "passive"))
    )
    (net (code "63") (name "Net-(U6A-XOUT{slash}PB8)") (class "Default")
      (node (ref "C25") (pin "2") (pinfunction "2_2") (pintype "passive"))
      (node (ref "U6") (pin "61") (pinfunction "XOUT/PB8_61") (pintype "bidirectional"))
      (node (ref "Y2") (pin "3") (pinfunction "OSC2_3") (pintype "passive"))
    )
    (net (code "64") (name "Net-(U6B-VDDOUT)") (class "Default")
      (node (ref "C30") (pin "1") (pinfunction "1_1") (pintype "passive"))
      (node (ref "C32") (pin "1") (pinfunction "1_1") (pintype "passive"))
      (node (ref "C34") (pin "1") (pinfunction "1_1") (pintype "passive"))
      (node (ref "C36") (pin "1") (pinfunction "1_1") (pintype "passive"))
      (node (ref "L4") (pin "2") (pinfunction "2_2") (pintype "passive"))
      (node (ref "U6") (pin "12") (pinfunction "VDDCORE_12") (pintype "power_in"))
      (node (ref "U6") (pin "24") (pinfunction "VDDCORE_24") (pintype "power_in"))
      (node (ref "U6") (pin "54") (pinfunction "VDDCORE_54") (pintype "power_in"))
      (node (ref "U6") (pin "8") (pinfunction "VDDOUT_8") (pintype "power_in"))
    )
    (net (code "65") (name "Net-(U6B-VDDPLL)") (class "Default")
      (node (ref "C39") (pin "2") (pinfunction "2_2") (pintype "passive"))
      (node (ref "C40") (pin "2") (pinfunction "2_2") (pintype "passive"))
      (node (ref "L4") (pin "1") (pinfunction "1_1") (pintype "passive"))
      (node (ref "U6") (pin "64") (pinfunction "VDDPLL_64") (pintype "power_in"))
    )
    (net (code "66") (name "Net-(U7-BST)") (class "Default")
      (node (ref "C26") (pin "1") (pinfunction "1_1") (pintype "passive"))
      (node (ref "U7") (pin "1") (pinfunction "BST_1") (pintype "passive"))
    )
    (net (code "67") (name "Net-(U7-PGOOD)") (class "Default")
      (node (ref "R14") (pin "1") (pinfunction "1_1") (pintype "passive"))
      (node (ref "U7") (pin "4") (pinfunction "PGOOD_4") (pintype "output"))
    )
    (net (code "68") (name "Net-(U8-VCC)") (class "Default")
      (node (ref "C38") (pin "2") (pinfunction "2_2") (pintype "passive"))
      (node (ref "R15") (pin "2") (pinfunction "2_2") (pintype "passive"))
      (node (ref "U8") (pin "1") (pinfunction "VCC_1") (pintype "passive"))
    )
    (net (code "69") (name "Net-(U9-OUT)") (class "Default")
      (node (ref "C42") (pin "2") (pinfunction "2_2") (pintype "passive"))
      (node (ref "R11") (pin "1") (pinfunction "1_1") (pintype "passive"))
      (node (ref "U9") (pin "5") (pinfunction "OUT_5") (pintype "power_in"))
    )
    (net (code "70") (name "Net-(U10-OUT)") (class "Default")
      (node (ref "C44") (pin "2") (pinfunction "2_2") (pintype "passive"))
      (node (ref "R16") (pin "1") (pinfunction "1_1") (pintype "passive"))
      (node (ref "U10") (pin "5") (pinfunction "OUT_5") (pintype "power_in"))
    )
    (net (code "71") (name "USB_DETECT") (class "Default")
      (node (ref "R19") (pin "1") (pinfunction "1_1") (pintype "passive"))
      (node (ref "R20") (pin "2") (pinfunction "2_2") (pintype "passive"))
      (node (ref "U6") (pin "35") (pinfunction "PA5/PGMRDY_35") (pintype "bidirectional"))
      (node (ref "USB_DETECT_TP1") (pin "1") (pinfunction "1_1") (pintype "passive"))
    )
    (net (code "72") (name "VBUS") (class "Default")
      (node (ref "D2") (pin "1") (pinfunction "A_1") (pintype "passive"))
      (node (ref "H8") (pin "1") (pinfunction "VBUS_1") (pintype "power_in"))
      (node (ref "R19") (pin "2") (pinfunction "2_2") (pintype "passive"))
      (node (ref "R8") (pin "2") (pinfunction "2_2") (pintype "passive"))
      (node (ref "VBUS_TP1") (pin "1") (pinfunction "1_1") (pintype "passive"))
    )
    (net (code "73") (name "V_BAT") (class "Default")
      (node (ref "C4") (pin "2") (pinfunction "2_2") (pintype "passive"))
      (node (ref "H3") (pin "5") (pinfunction "5_5") (pintype "passive"))
      (node (ref "R14") (pin "2") (pinfunction "2_2") (pintype "passive"))
      (node (ref "R6") (pin "2") (pinfunction "2_2") (pintype "passive"))
      (node (ref "R9") (pin "2") (pinfunction "2_2") (pintype "passive"))
      (node (ref "U7") (pin "2") (pinfunction "VIN_2") (pintype "input"))
      (node (ref "U7") (pin "3") (pinfunction "EN_3") (pintype "output"))
      (node (ref "V_BATT_TP1") (pin "1") (pinfunction "1_1") (pintype "passive"))
    )
    (net (code "74") (name "unconnected-(H8-ID-Pad4)") (class "Default")
      (node (ref "H8") (pin "4") (pinfunction "ID_4") (pintype "power_in"))
    )
    (net (code "75") (name "unconnected-(H9-Pad3)") (class "Default")
      (node (ref "H9") (pin "3") (pinfunction "3_3") (pintype "passive+no_connect"))
    )
    (net (code "76") (name "unconnected-(H9-Pad9)") (class "Default")
      (node (ref "H9") (pin "9") (pinfunction "9_9") (pintype "passive+no_connect"))
    )
    (net (code "77") (name "unconnected-(H9-Pad10)") (class "Default")
      (node (ref "H9") (pin "10") (pinfunction "10_10") (pintype "passive+no_connect"))
    )
    (net (code "78") (name "unconnected-(U1-AUX_CL-Pad7)") (class "Default")
      (node (ref "U1") (pin "7") (pinfunction "AUX_CL_7") (pintype "passive+no_connect"))
    )
    (net (code "79") (name "unconnected-(U1-AUX_DA-Pad21)") (class "Default")
      (node (ref "U1") (pin "21") (pinfunction "AUX_DA_21") (pintype "passive+no_connect"))
    )
    (net (code "80") (name "unconnected-(U1-INT-Pad12)") (class "Default")
      (node (ref "U1") (pin "12") (pinfunction "INT_12") (pintype "passive+no_connect"))
    )
    (net (code "81") (name "unconnected-(U6A-JTAGSEL-Pad50)") (class "Default")
      (node (ref "U6") (pin "50") (pinfunction "JTAGSEL_50") (pintype "input+no_connect"))
    )
    (net (code "82") (name "unconnected-(U6A-TDI{slash}PB4-Pad33)") (class "Default")
      (node (ref "U6") (pin "33") (pinfunction "TDI/PB4_33") (pintype "bidirectional+no_connect"))
    )
    (net (code "83") (name "unconnected-(U6A-TDO{slash}TRACESWO{slash}PB5-Pad49)") (class "Default")
      (node (ref "U6") (pin "49") (pinfunction "TDO/TRACESWO/PB5_49") (pintype "bidirectional+no_connect"))
    )
    (net (code "84") (name "unconnected-(U6A-TST-Pad40)") (class "Default")
      (node (ref "U6") (pin "40") (pinfunction "TST_40") (pintype "input+no_connect"))
    )
    (net (code "85") (name "unconnected-(U7-NC-Pad6)") (class "Default")
      (node (ref "U7") (pin "6") (pinfunction "NC_6") (pintype "passive+no_connect"))
    )
    (net (code "86") (name "unconnected-(U9-BYP-Pad4)") (class "Default")
      (node (ref "U9") (pin "4") (pinfunction "BYP_4") (pintype "passive"))
    )
    (net (code "87") (name "unconnected-(U10-BYP-Pad4)") (class "Default")
      (node (ref "U10") (pin "4") (pinfunction "BYP_4") (pintype "passive"))
    )
    (net (code "88") (name "unconnected-(VR1-Pad9)") (class "Default")
      (node (ref "VR1") (pin "9") (pinfunction "9_9") (pintype "passive+no_connect"))
    )
    (net (code "89") (name "unconnected-(VR1-Pad10)") (class "Default")
      (node (ref "VR1") (pin "10") (pinfunction "10_10") (pintype "passive+no_connect"))
    )
  )
)
